# mpx20xx.net
KiCad netlist of a schematic drawn in EAGLE
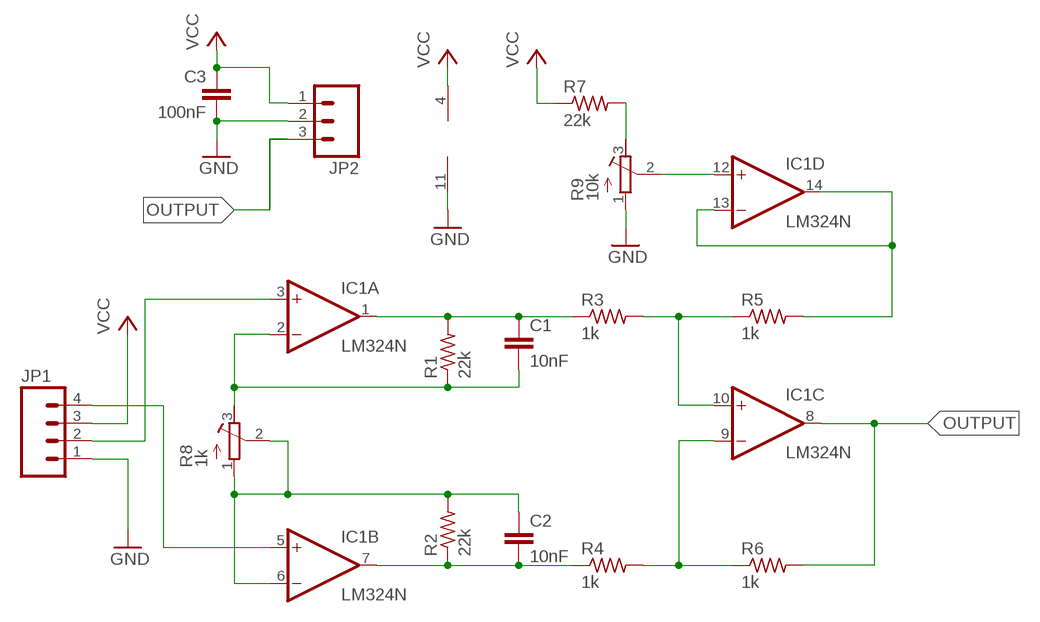
[diagram p0: schematic, sheet 1]

(export (version "E")
  (design (tool "Eeschema 10.0.6"))
  (components
    (comp (ref "C1")
      (value "10nF")
      (footprint "eagle-import:C050-025X075")
      (libsource (lib "eagle-import") (part "C-EU050-025X075"))
    )
    (comp (ref "C2")
      (value "10nF")
      (footprint "eagle-import:C050-025X075")
      (libsource (lib "eagle-import") (part "C-EU050-025X075"))
    )
    (comp (ref "C3")
      (value "100nF")
      (footprint "eagle-import:C050-025X075")
      (libsource (lib "eagle-import") (part "C-EU050-025X075"))
    )
    (comp (ref "IC1")
      (value "LM324N")
      (footprint "eagle-import:DIL14")
      (libsource (lib "eagle-import") (part "LM324N"))
    )
    (comp (ref "JP1")
      (value "M04LONGPADS")
      (footprint "eagle-import:1X04_LONGPADS")
      (libsource (lib "eagle-import") (part "M04LONGPADS"))
    )
    (comp (ref "JP2")
      (value "M03LONGPADS")
      (footprint "eagle-import:1X03_LONGPADS")
      (libsource (lib "eagle-import") (part "M03LONGPADS"))
    )
    (comp (ref "R1")
      (value "22k")
      (footprint "eagle-import:0207_10")
      (libsource (lib "eagle-import") (part "R-US_0207/10"))
    )
    (comp (ref "R2")
      (value "22k")
      (footprint "eagle-import:0207_10")
      (libsource (lib "eagle-import") (part "R-US_0207/10"))
    )
    (comp (ref "R3")
      (value "1k")
      (footprint "eagle-import:0207_10")
      (libsource (lib "eagle-import") (part "R-US_0207/10"))
    )
    (comp (ref "R4")
      (value "1k")
      (footprint "eagle-import:0207_10")
      (libsource (lib "eagle-import") (part "R-US_0207/10"))
    )
    (comp (ref "R5")
      (value "1k")
      (footprint "eagle-import:0207_10")
      (libsource (lib "eagle-import") (part "R-US_0207/10"))
    )
    (comp (ref "R6")
      (value "1k")
      (footprint "eagle-import:0207_10")
      (libsource (lib "eagle-import") (part "R-US_0207/10"))
    )
    (comp (ref "R7")
      (value "22k")
      (footprint "eagle-import:0207_10")
      (libsource (lib "eagle-import") (part "R-US_0207/10"))
    )
    (comp (ref "R8")
      (value "1k")
      (footprint "eagle-import:RTRIM3299W")
      (libsource (lib "eagle-import") (part "R-TRIMM3299W"))
    )
    (comp (ref "R9")
      (value "10k")
      (footprint "eagle-import:RTRIM3299W")
      (libsource (lib "eagle-import") (part "R-TRIMM3299W"))
    )
  )
  (nets
    (net (code "1") (name "GND") (class "Default")
      (node (ref "C3") (pin "2") (pinfunction "2_2") (pintype "passive"))
      (node (ref "IC1") (pin "11") (pinfunction "V-_11") (pintype "power_in"))
      (node (ref "JP1") (pin "1") (pinfunction "1_1") (pintype "passive"))
      (node (ref "JP2") (pin "2") (pinfunction "2_2") (pintype "passive"))
      (node (ref "R9") (pin "1") (pinfunction "A_1") (pintype "passive"))
    )
    (net (code "2") (name "Net-(IC1A-+IN)") (class "Default")
      (node (ref "IC1") (pin "3") (pinfunction "+IN_3") (pintype "input"))
      (node (ref "JP1") (pin "2") (pinfunction "2_2") (pintype "passive"))
    )
    (net (code "3") (name "Net-(IC1A--IN)") (class "Default")
      (node (ref "C1") (pin "2") (pinfunction "2_2") (pintype "passive"))
      (node (ref "IC1") (pin "2") (pinfunction "-IN_2") (pintype "input"))
      (node (ref "R1") (pin "1") (pinfunction "1_1") (pintype "passive"))
      (node (ref "R8") (pin "3") (pinfunction "E_3") (pintype "passive"))
    )
    (net (code "4") (name "Net-(IC1A-OUT)") (class "Default")
      (node (ref "C1") (pin "1") (pinfunction "1_1") (pintype "passive"))
      (node (ref "IC1") (pin "1") (pinfunction "OUT_1") (pintype "output"))
      (node (ref "R1") (pin "2") (pinfunction "2_2") (pintype "passive"))
      (node (ref "R3") (pin "1") (pinfunction "1_1") (pintype "passive"))
    )
    (net (code "5") (name "Net-(IC1B-+IN)") (class "Default")
      (node (ref "IC1") (pin "5") (pinfunction "+IN_5") (pintype "input"))
      (node (ref "JP1") (pin "4") (pinfunction "4_4") (pintype "passive"))
    )
    (net (code "6") (name "Net-(IC1B--IN)") (class "Default")
      (node (ref "C2") (pin "1") (pinfunction "1_1") (pintype "passive"))
      (node (ref "IC1") (pin "6") (pinfunction "-IN_6") (pintype "input"))
      (node (ref "R2") (pin "2") (pinfunction "2_2") (pintype "passive"))
      (node (ref "R8") (pin "1") (pinfunction "A_1") (pintype "passive"))
      (node (ref "R8") (pin "2") (pinfunction "S_2") (pintype "passive"))
    )
    (net (code "7") (name "Net-(IC1B-OUT)") (class "Default")
      (node (ref "C2") (pin "2") (pinfunction "2_2") (pintype "passive"))
      (node (ref "IC1") (pin "7") (pinfunction "OUT_7") (pintype "output"))
      (node (ref "R2") (pin "1") (pinfunction "1_1") (pintype "passive"))
      (node (ref "R4") (pin "1") (pinfunction "1_1") (pintype "passive"))
    )
    (net (code "8") (name "Net-(IC1C-+IN)") (class "Default")
      (node (ref "IC1") (pin "10") (pinfunction "+IN_10") (pintype "input"))
      (node (ref "R3") (pin "2") (pinfunction "2_2") (pintype "passive"))
      (node (ref "R5") (pin "1") (pinfunction "1_1") (pintype "passive"))
    )
    (net (code "9") (name "Net-(IC1C--IN)") (class "Default")
      (node (ref "IC1") (pin "9") (pinfunction "-IN_9") (pintype "input"))
      (node (ref "R4") (pin "2") (pinfunction "2_2") (pintype "passive"))
      (node (ref "R6") (pin "1") (pinfunction "1_1") (pintype "passive"))
    )
    (net (code "10") (name "Net-(IC1D-+IN)") (class "Default")
      (node (ref "IC1") (pin "12") (pinfunction "+IN_12") (pintype "input"))
      (node (ref "R9") (pin "2") (pinfunction "S_2") (pintype "passive"))
    )
    (net (code "11") (name "Net-(IC1D--IN)") (class "Default")
      (node (ref "IC1") (pin "13") (pinfunction "-IN_13") (pintype "input"))
      (node (ref "IC1") (pin "14") (pinfunction "OUT_14") (pintype "output"))
      (node (ref "R5") (pin "2") (pinfunction "2_2") (pintype "passive"))
    )
    (net (code "12") (name "Net-(R9-E)") (class "Default")
      (node (ref "R7") (pin "2") (pinfunction "2_2") (pintype "passive"))
      (node (ref "R9") (pin "3") (pinfunction "E_3") (pintype "passive"))
    )
    (net (code "13") (name "OUTPUT") (class "Default")
      (node (ref "IC1") (pin "8") (pinfunction "OUT_8") (pintype "output"))
      (node (ref "JP2") (pin "3") (pinfunction "3_3") (pintype "passive"))
      (node (ref "R6") (pin "2") (pinfunction "2_2") (pintype "passive"))
    )
    (net (code "14") (name "VCC") (class "Default")
      (node (ref "C3") (pin "1") (pinfunction "1_1") (pintype "passive"))
      (node (ref "IC1") (pin "4") (pinfunction "V+_4") (pintype "power_in"))
      (node (ref "JP1") (pin "3") (pinfunction "3_3") (pintype "passive"))
      (node (ref "JP2") (pin "1") (pinfunction "1_1") (pintype "passive"))
      (node (ref "R7") (pin "1") (pinfunction "1_1") (pintype "passive"))
    )
  )
)
